# 04_CapTouch.net
KiCad netlist of a schematic drawn in Altium Designer
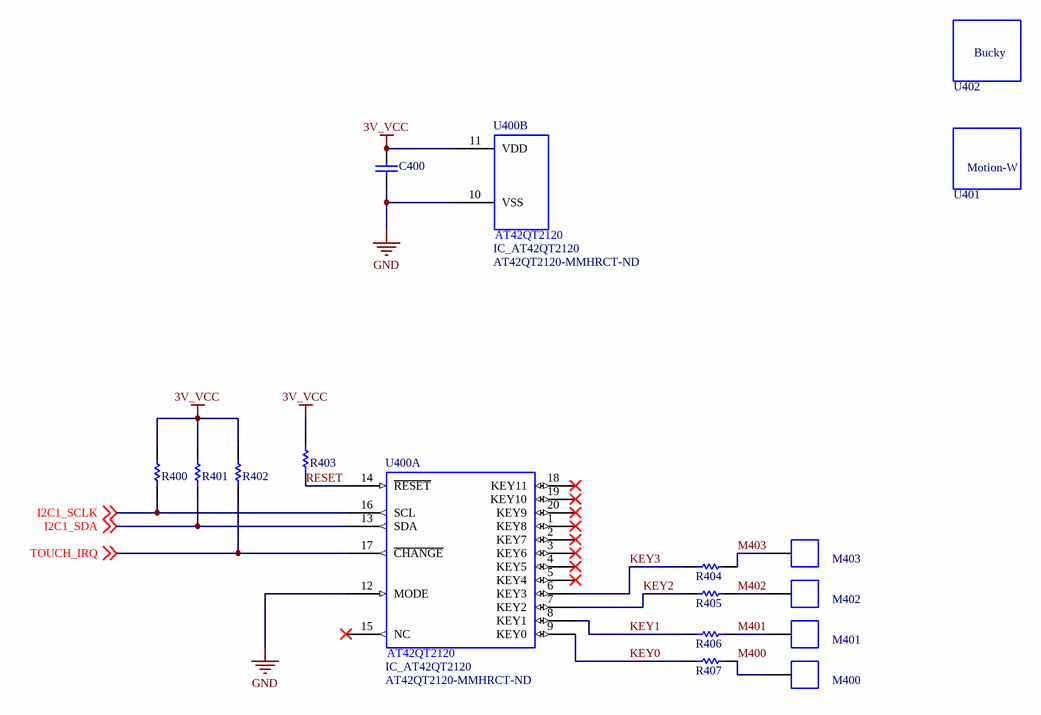
[diagram p0: 04_CapTouch.SchDoc]

(export (version "E")
  (design (tool "Eeschema 10.0.6"))
  (components
    (comp (ref "C400")
      (value "CAP_0805_U_001.00")
      (footprint "CAP_0805")
      (description "CAP CER 1UF 16V 10% X7R 0805")
      (fields
        (field (name "MANUFACTURER") "Yageo")
        (field (name "MANUFACTURER PART NUMBER") "CC0805KKX7R7BB105")
      )
      (libsource (lib "ece315") (part "CAP_0805_U_001.00"))
    )
    (comp (ref "M400")
      (value "Mech_TouchPad")
      (footprint "TouchPad")
      (description "Capacative Touch Sensor Pad")
      (libsource (lib "ece315-2017-fall") (part "Mech_TouchPad"))
    )
    (comp (ref "M401")
      (value "Mech_TouchPad")
      (footprint "TouchPad")
      (description "Capacative Touch Sensor Pad")
      (libsource (lib "ece315-2017-fall") (part "Mech_TouchPad"))
    )
    (comp (ref "M402")
      (value "Mech_TouchPad")
      (footprint "TouchPad")
      (description "Capacative Touch Sensor Pad")
      (libsource (lib "ece315-2017-fall") (part "Mech_TouchPad"))
    )
    (comp (ref "M403")
      (value "Mech_TouchPad")
      (footprint "TouchPad")
      (description "Capacative Touch Sensor Pad")
      (libsource (lib "ece315-2017-fall") (part "Mech_TouchPad"))
    )
    (comp (ref "R400")
      (value "RES_0805_R_562_00")
      (footprint "RES_0805")
      (description "RES SMD 562 OHM 1% 1/8W 0805")
      (fields
        (field (name "MANUFACTURER") "Yageo")
        (field (name "MANUFACTURER PART NUMBER") "RC0805FR-07562RL")
      )
      (libsource (lib "ece315") (part "RES_0805_R_562_00"))
    )
    (comp (ref "R401")
      (value "RES_0805_R_562_00")
      (footprint "RES_0805")
      (description "RES SMD 562 OHM 1% 1/8W 0805")
      (fields
        (field (name "MANUFACTURER") "Yageo")
        (field (name "MANUFACTURER PART NUMBER") "RC0805FR-07562RL")
      )
      (libsource (lib "ece315") (part "RES_0805_R_562_00"))
    )
    (comp (ref "R402")
      (value "RES_0805_R_562_00")
      (footprint "RES_0805")
      (description "RES SMD 562 OHM 1% 1/8W 0805")
      (fields
        (field (name "MANUFACTURER") "Yageo")
        (field (name "MANUFACTURER PART NUMBER") "RC0805FR-07562RL")
      )
      (libsource (lib "ece315") (part "RES_0805_R_562_00"))
    )
    (comp (ref "R403")
      (value "RES_0805_R_562_00")
      (footprint "RES_0805")
      (description "RES SMD 562 OHM 1% 1/8W 0805")
      (fields
        (field (name "MANUFACTURER") "Yageo")
        (field (name "MANUFACTURER PART NUMBER") "RC0805FR-07562RL")
      )
      (libsource (lib "ece315") (part "RES_0805_R_562_00"))
    )
    (comp (ref "R404")
      (value "RES_0805_R_562_00")
      (footprint "RES_0805")
      (description "RES SMD 562 OHM 1% 1/8W 0805")
      (fields
        (field (name "MANUFACTURER") "Yageo")
        (field (name "MANUFACTURER PART NUMBER") "RC0805FR-07562RL")
      )
      (libsource (lib "ece315") (part "RES_0805_R_562_00"))
    )
    (comp (ref "R405")
      (value "RES_0805_R_562_00")
      (footprint "RES_0805")
      (description "RES SMD 562 OHM 1% 1/8W 0805")
      (fields
        (field (name "MANUFACTURER") "Yageo")
        (field (name "MANUFACTURER PART NUMBER") "RC0805FR-07562RL")
      )
      (libsource (lib "ece315") (part "RES_0805_R_562_00"))
    )
    (comp (ref "R406")
      (value "RES_0805_R_562_00")
      (footprint "RES_0805")
      (description "RES SMD 562 OHM 1% 1/8W 0805")
      (fields
        (field (name "MANUFACTURER") "Yageo")
        (field (name "MANUFACTURER PART NUMBER") "RC0805FR-07562RL")
      )
      (libsource (lib "ece315") (part "RES_0805_R_562_00"))
    )
    (comp (ref "R407")
      (value "RES_0805_R_562_00")
      (footprint "RES_0805")
      (description "RES SMD 562 OHM 1% 1/8W 0805")
      (fields
        (field (name "MANUFACTURER") "Yageo")
        (field (name "MANUFACTURER PART NUMBER") "RC0805FR-07562RL")
      )
      (libsource (lib "ece315") (part "RES_0805_R_562_00"))
    )
    (comp (ref "U400")
      (value "IC_AT42QT2120")
      (footprint "IC_AT42QT2120")
      (fields
        (field (name "MANUFACTURER") "Microchip Technology")
        (field (name "MANUFACTURER PART NUMBER") "AT42QT2120-MMHR")
        (field (name "SUPPLIER PART NUMBER 1") "AT42QT2120-MMHRCT-ND")
      )
      (libsource (lib "ece315") (part "IC_AT42QT2120"))
    )
    (comp (ref "U401")
      (value "Motion_W")
      (footprint "Motion_W")
      (description "Motion W Image")
      (fields (field (name "MANUFACTURER PART NUMBER") "UW Bucky"))
      (libsource (lib "ece315-2017-fall") (part "Motion_W"))
    )
    (comp (ref "U402")
      (value "Bucky")
      (footprint "BuckyBadger")
      (description "Bucky Badger Image")
      (fields (field (name "MANUFACTURER PART NUMBER") "UW Bucky"))
      (libsource (lib "ece315-2017-fall") (part "Bucky"))
    )
  )
  (nets
    (net (code "1") (name "/KEY0") (class "Default")
      (node (ref "R407") (pin "1") (pinfunction "1_1") (pintype "passive"))
      (node (ref "U400") (pin "9") (pinfunction "KEY0_9") (pintype "bidirectional"))
    )
    (net (code "2") (name "/KEY1") (class "Default")
      (node (ref "R406") (pin "1") (pinfunction "1_1") (pintype "passive"))
      (node (ref "U400") (pin "8") (pinfunction "KEY1_8") (pintype "bidirectional"))
    )
    (net (code "3") (name "/KEY2") (class "Default")
      (node (ref "R405") (pin "1") (pinfunction "1_1") (pintype "passive"))
      (node (ref "U400") (pin "7") (pinfunction "KEY2_7") (pintype "bidirectional"))
    )
    (net (code "4") (name "/KEY3") (class "Default")
      (node (ref "R404") (pin "1") (pinfunction "1_1") (pintype "passive"))
      (node (ref "U400") (pin "6") (pinfunction "KEY3_6") (pintype "bidirectional"))
    )
    (net (code "5") (name "/M400") (class "Default")
      (node (ref "M400") (pin "1") (pinfunction "1_1") (pintype "passive"))
      (node (ref "R407") (pin "2") (pinfunction "2_2") (pintype "passive"))
    )
    (net (code "6") (name "/M401") (class "Default")
      (node (ref "M401") (pin "1") (pinfunction "1_1") (pintype "passive"))
      (node (ref "R406") (pin "2") (pinfunction "2_2") (pintype "passive"))
    )
    (net (code "7") (name "/M402") (class "Default")
      (node (ref "M402") (pin "1") (pinfunction "1_1") (pintype "passive"))
      (node (ref "R405") (pin "2") (pinfunction "2_2") (pintype "passive"))
    )
    (net (code "8") (name "/M403") (class "Default")
      (node (ref "M403") (pin "1") (pinfunction "1_1") (pintype "passive"))
      (node (ref "R404") (pin "2") (pinfunction "2_2") (pintype "passive"))
    )
    (net (code "9") (name "/RESET") (class "Default")
      (node (ref "R403") (pin "1") (pinfunction "1_1") (pintype "passive"))
      (node (ref "U400") (pin "14") (pinfunction "~{RESET}_14") (pintype "input"))
    )
    (net (code "10") (name "3V_VCC") (class "Default")
      (node (ref "C400") (pin "1") (pinfunction "1_1") (pintype "passive"))
      (node (ref "R400") (pin "2") (pinfunction "2_2") (pintype "passive"))
      (node (ref "R401") (pin "2") (pinfunction "2_2") (pintype "passive"))
      (node (ref "R402") (pin "2") (pinfunction "2_2") (pintype "passive"))
      (node (ref "R403") (pin "2") (pinfunction "2_2") (pintype "passive"))
      (node (ref "U400") (pin "11") (pinfunction "VDD_11") (pintype "power_in"))
    )
    (net (code "11") (name "GND") (class "Default")
      (node (ref "C400") (pin "2") (pinfunction "2_2") (pintype "passive"))
      (node (ref "U400") (pin "10") (pinfunction "VSS_10") (pintype "power_in"))
      (node (ref "U400") (pin "12") (pinfunction "MODE_12") (pintype "input"))
    )
    (net (code "12") (name "I2C1_SCLK") (class "Default")
      (node (ref "R400") (pin "1") (pinfunction "1_1") (pintype "passive"))
      (node (ref "U400") (pin "16") (pinfunction "SCL_16") (pintype "output"))
    )
    (net (code "13") (name "I2C1_SDA") (class "Default")
      (node (ref "R401") (pin "1") (pinfunction "1_1") (pintype "passive"))
      (node (ref "U400") (pin "13") (pinfunction "SDA_13") (pintype "output"))
    )
    (net (code "14") (name "TOUCH_IRQ") (class "Default")
      (node (ref "R402") (pin "1") (pinfunction "1_1") (pintype "passive"))
      (node (ref "U400") (pin "17") (pinfunction "~{CHANGE}_17") (pintype "output"))
    )
    (net (code "15") (name "unconnected-(U400A-KEY4-Pad5)") (class "Default")
      (node (ref "U400") (pin "5") (pinfunction "KEY4_5") (pintype "bidirectional+no_connect"))
    )
    (net (code "16") (name "unconnected-(U400A-KEY5-Pad4)") (class "Default")
      (node (ref "U400") (pin "4") (pinfunction "KEY5_4") (pintype "bidirectional+no_connect"))
    )
    (net (code "17") (name "unconnected-(U400A-KEY6-Pad3)") (class "Default")
      (node (ref "U400") (pin "3") (pinfunction "KEY6_3") (pintype "bidirectional+no_connect"))
    )
    (net (code "18") (name "unconnected-(U400A-KEY7-Pad2)") (class "Default")
      (node (ref "U400") (pin "2") (pinfunction "KEY7_2") (pintype "bidirectional+no_connect"))
    )
    (net (code "19") (name "unconnected-(U400A-KEY8-Pad1)") (class "Default")
      (node (ref "U400") (pin "1") (pinfunction "KEY8_1") (pintype "bidirectional+no_connect"))
    )
    (net (code "20") (name "unconnected-(U400A-KEY9-Pad20)") (class "Default")
      (node (ref "U400") (pin "20") (pinfunction "KEY9_20") (pintype "bidirectional+no_connect"))
    )
    (net (code "21") (name "unconnected-(U400A-KEY10-Pad19)") (class "Default")
      (node (ref "U400") (pin "19") (pinfunction "KEY10_19") (pintype "bidirectional+no_connect"))
    )
    (net (code "22") (name "unconnected-(U400A-KEY11-Pad18)") (class "Default")
      (node (ref "U400") (pin "18") (pinfunction "KEY11_18") (pintype "bidirectional+no_connect"))
    )
    (net (code "23") (name "unconnected-(U400A-NC-Pad15)") (class "Default")
      (node (ref "U400") (pin "15") (pinfunction "NC_15") (pintype "output+no_connect"))
    )
  )
)
